# ProtoAcc_l_rotronLLLetMAS_Circuit.net
KiCad netlist of a schematic drawn in Altium Designer
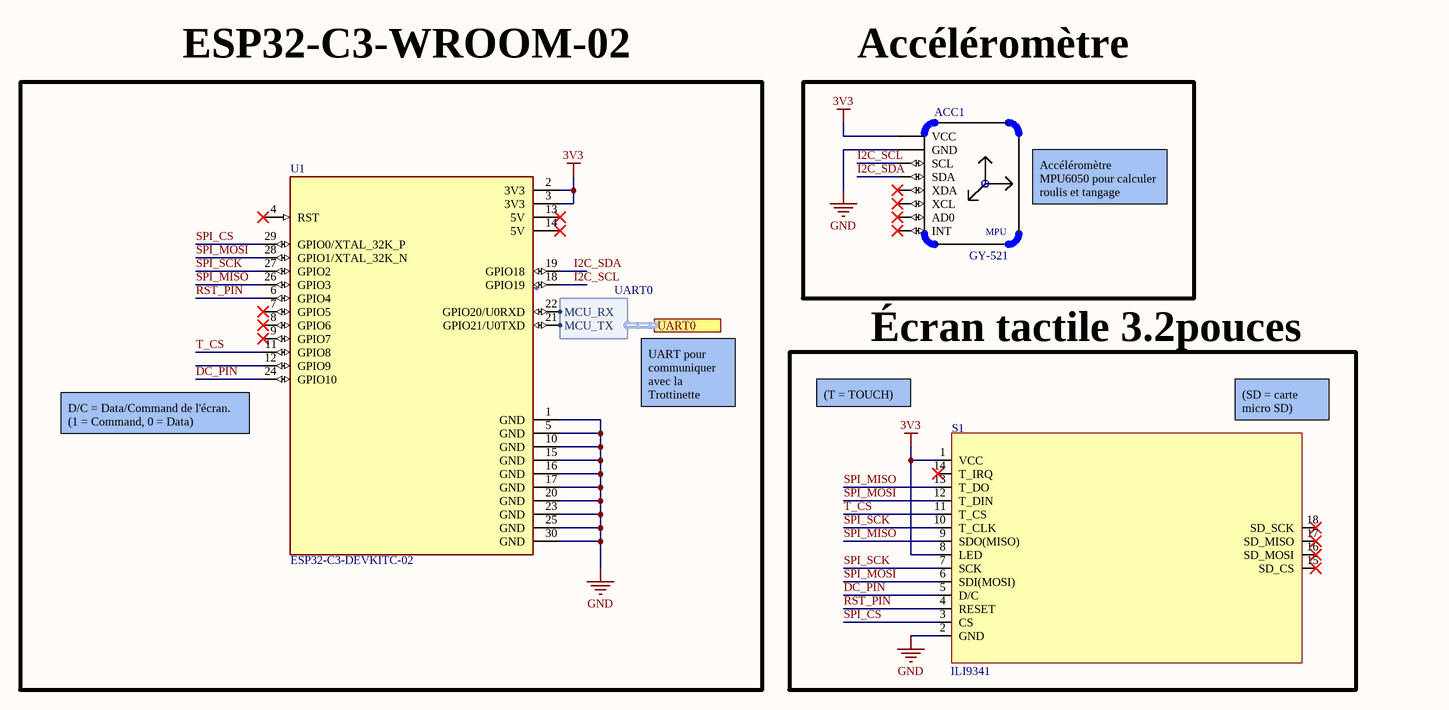
[diagram p0: ProtoAccélérotronLLLetMAS_Circuit.SchDoc]

(export (version "E")
  (design (tool "Eeschema 10.0.6"))
  (components
    (comp (ref "ACC1")
      (value "GY-521")
      (footprint "*GY-521_GY-521(Primary)")
      (description "Triple Axis Accelerometer Gyro Breakout")
      (fields (field (name "MF") "GODREAM FORDREAM CO., LIMITED"))
      (libsource (lib "GY-521") (part "GY-521"))
    )
    (comp (ref "S1")
      (value "ILI9341")
      (description "3.2\" 240x320 TFT LCD ILI9341")
      (libsource (lib "ILI9341") (part "ILI9341"))
    )
    (comp (ref "U1")
      (value "ESP32-C3-DEVKITC-02")
      (footprint "XCVR_ESP32-C3-DEVKITC-02")
      (fields (field (name "MP") "ESP32-C3-DevKitC-02") (field (name "MF") "Espressif Systems"))
      (libsource (lib "ESP32-C3-DEVKITC-02") (part "ESP32-C3-DEVKITC-02"))
    )
  )
  (nets
    (net (code "2") (name "/DC_PIN") (class "Default")
      (node (ref "S1") (pin "5") (pinfunction "D/C_5") (pintype "passive"))
      (node (ref "U1") (pin "24") (pinfunction "GPIO10_24") (pintype "bidirectional"))
    )
    (net (code "3") (name "/I2C_SCL") (class "Default")
      (node (ref "ACC1") (pin "SCL") (pinfunction "SCL_SCL") (pintype "bidirectional"))
      (node (ref "U1") (pin "18") (pinfunction "GPIO19_18") (pintype "bidirectional"))
    )
    (net (code "4") (name "/I2C_SDA") (class "Default")
      (node (ref "ACC1") (pin "SDA") (pinfunction "SDA_SDA") (pintype "bidirectional"))
      (node (ref "U1") (pin "19") (pinfunction "GPIO18_19") (pintype "bidirectional"))
    )
    (net (code "5") (name "/MCU_RX") (class "Default")
      (node (ref "U1") (pin "22") (pinfunction "GPIO20/U0RXD_22") (pintype "bidirectional"))
    )
    (net (code "6") (name "/MCU_TX") (class "Default")
      (node (ref "U1") (pin "21") (pinfunction "GPIO21/U0TXD_21") (pintype "bidirectional"))
    )
    (net (code "7") (name "/RST_PIN") (class "Default")
      (node (ref "S1") (pin "4") (pinfunction "RESET_4") (pintype "passive"))
      (node (ref "U1") (pin "6") (pinfunction "GPIO4_6") (pintype "bidirectional"))
    )
    (net (code "8") (name "/SPI_CS") (class "Default")
      (node (ref "S1") (pin "3") (pinfunction "CS_3") (pintype "passive"))
      (node (ref "U1") (pin "29") (pinfunction "GPIO0/XTAL_32K_P_29") (pintype "bidirectional"))
    )
    (net (code "9") (name "/SPI_MISO") (class "Default")
      (node (ref "S1") (pin "13") (pinfunction "T_DO_13") (pintype "passive"))
      (node (ref "S1") (pin "9") (pinfunction "SDO(MISO)_9") (pintype "passive"))
      (node (ref "U1") (pin "26") (pinfunction "GPIO3_26") (pintype "bidirectional"))
    )
    (net (code "10") (name "/SPI_MOSI") (class "Default")
      (node (ref "S1") (pin "12") (pinfunction "T_DIN_12") (pintype "passive"))
      (node (ref "S1") (pin "6") (pinfunction "SDI(MOSI)_6") (pintype "passive"))
      (node (ref "U1") (pin "28") (pinfunction "GPIO1/XTAL_32K_N_28") (pintype "bidirectional"))
    )
    (net (code "11") (name "/SPI_SCK") (class "Default")
      (node (ref "S1") (pin "10") (pinfunction "T_CLK_10") (pintype "passive"))
      (node (ref "S1") (pin "7") (pinfunction "SCK_7") (pintype "passive"))
      (node (ref "U1") (pin "27") (pinfunction "GPIO2_27") (pintype "bidirectional"))
    )
    (net (code "12") (name "/T_CS") (class "Default")
      (node (ref "S1") (pin "11") (pinfunction "T_CS_11") (pintype "passive"))
      (node (ref "U1") (pin "11") (pinfunction "GPIO8_11") (pintype "bidirectional"))
    )
    (net (code "14") (name "3V3") (class "Default")
      (node (ref "ACC1") (pin "VCC") (pinfunction "VCC_VCC") (pintype "power_in"))
      (node (ref "S1") (pin "1") (pinfunction "VCC_1") (pintype "passive"))
      (node (ref "S1") (pin "8") (pinfunction "LED_8") (pintype "passive"))
      (node (ref "U1") (pin "2") (pinfunction "3V3_2") (pintype "power_in"))
      (node (ref "U1") (pin "3") (pinfunction "3V3_3") (pintype "power_in"))
    )
    (net (code "15") (name "GND") (class "Default")
      (node (ref "ACC1") (pin "GND") (pinfunction "GND_GND") (pintype "power_in"))
      (node (ref "S1") (pin "2") (pinfunction "GND_2") (pintype "passive"))
      (node (ref "U1") (pin "1") (pinfunction "GND_1") (pintype "power_in"))
      (node (ref "U1") (pin "10") (pinfunction "GND_10") (pintype "power_in"))
      (node (ref "U1") (pin "15") (pinfunction "GND_15") (pintype "power_in"))
      (node (ref "U1") (pin "16") (pinfunction "GND_16") (pintype "power_in"))
      (node (ref "U1") (pin "17") (pinfunction "GND_17") (pintype "power_in"))
      (node (ref "U1") (pin "20") (pinfunction "GND_20") (pintype "power_in"))
      (node (ref "U1") (pin "23") (pinfunction "GND_23") (pintype "power_in"))
      (node (ref "U1") (pin "25") (pinfunction "GND_25") (pintype "power_in"))
      (node (ref "U1") (pin "30") (pinfunction "GND_30") (pintype "power_in"))
      (node (ref "U1") (pin "5") (pinfunction "GND_5") (pintype "power_in"))
    )
    (net (code "16") (name "unconnected-(ACC1-PadAD0)") (class "Default")
      (node (ref "ACC1") (pin "AD0") (pinfunction "AD0_AD0") (pintype "bidirectional+no_connect"))
    )
    (net (code "17") (name "unconnected-(ACC1-PadINT)") (class "Default")
      (node (ref "ACC1") (pin "INT") (pinfunction "INT_INT") (pintype "bidirectional+no_connect"))
    )
    (net (code "18") (name "unconnected-(ACC1-PadXCL)") (class "Default")
      (node (ref "ACC1") (pin "XCL") (pinfunction "XCL_XCL") (pintype "bidirectional+no_connect"))
    )
    (net (code "19") (name "unconnected-(ACC1-PadXDA)") (class "Default")
      (node (ref "ACC1") (pin "XDA") (pinfunction "XDA_XDA") (pintype "bidirectional+no_connect"))
    )
    (net (code "20") (name "unconnected-(S1-SD_CS-Pad15)") (class "Default")
      (node (ref "S1") (pin "15") (pinfunction "SD_CS_15") (pintype "passive+no_connect"))
    )
    (net (code "21") (name "unconnected-(S1-SD_MISO-Pad17)") (class "Default")
      (node (ref "S1") (pin "17") (pinfunction "SD_MISO_17") (pintype "passive+no_connect"))
    )
    (net (code "22") (name "unconnected-(S1-SD_MOSI-Pad16)") (class "Default")
      (node (ref "S1") (pin "16") (pinfunction "SD_MOSI_16") (pintype "passive+no_connect"))
    )
    (net (code "23") (name "unconnected-(S1-SD_SCK-Pad18)") (class "Default")
      (node (ref "S1") (pin "18") (pinfunction "SD_SCK_18") (pintype "passive+no_connect"))
    )
    (net (code "24") (name "unconnected-(S1-T_IRQ-Pad14)") (class "Default")
      (node (ref "S1") (pin "14") (pinfunction "T_IRQ_14") (pintype "passive+no_connect"))
    )
    (net (code "25") (name "unconnected-(U1-5V-Pad13)") (class "Default")
      (node (ref "U1") (pin "13") (pinfunction "5V_13") (pintype "power_in+no_connect"))
    )
    (net (code "26") (name "unconnected-(U1-5V-Pad14)") (class "Default")
      (node (ref "U1") (pin "14") (pinfunction "5V_14") (pintype "power_in+no_connect"))
    )
    (net (code "27") (name "unconnected-(U1-GPIO5-Pad7)") (class "Default")
      (node (ref "U1") (pin "7") (pinfunction "GPIO5_7") (pintype "bidirectional+no_connect"))
    )
    (net (code "28") (name "unconnected-(U1-GPIO6-Pad8)") (class "Default")
      (node (ref "U1") (pin "8") (pinfunction "GPIO6_8") (pintype "bidirectional+no_connect"))
    )
    (net (code "29") (name "unconnected-(U1-GPIO7-Pad9)") (class "Default")
      (node (ref "U1") (pin "9") (pinfunction "GPIO7_9") (pintype "bidirectional+no_connect"))
    )
    (net (code "30") (name "unconnected-(U1-GPIO9-Pad12)") (class "Default")
      (node (ref "U1") (pin "12") (pinfunction "GPIO9_12") (pintype "bidirectional"))
    )
    (net (code "31") (name "unconnected-(U1-RST-Pad4)") (class "Default")
      (node (ref "U1") (pin "4") (pinfunction "RST_4") (pintype "input+no_connect"))
    )
  )
)
